# FuseCircuit.net
KiCad netlist of a schematic drawn in Altium Designer
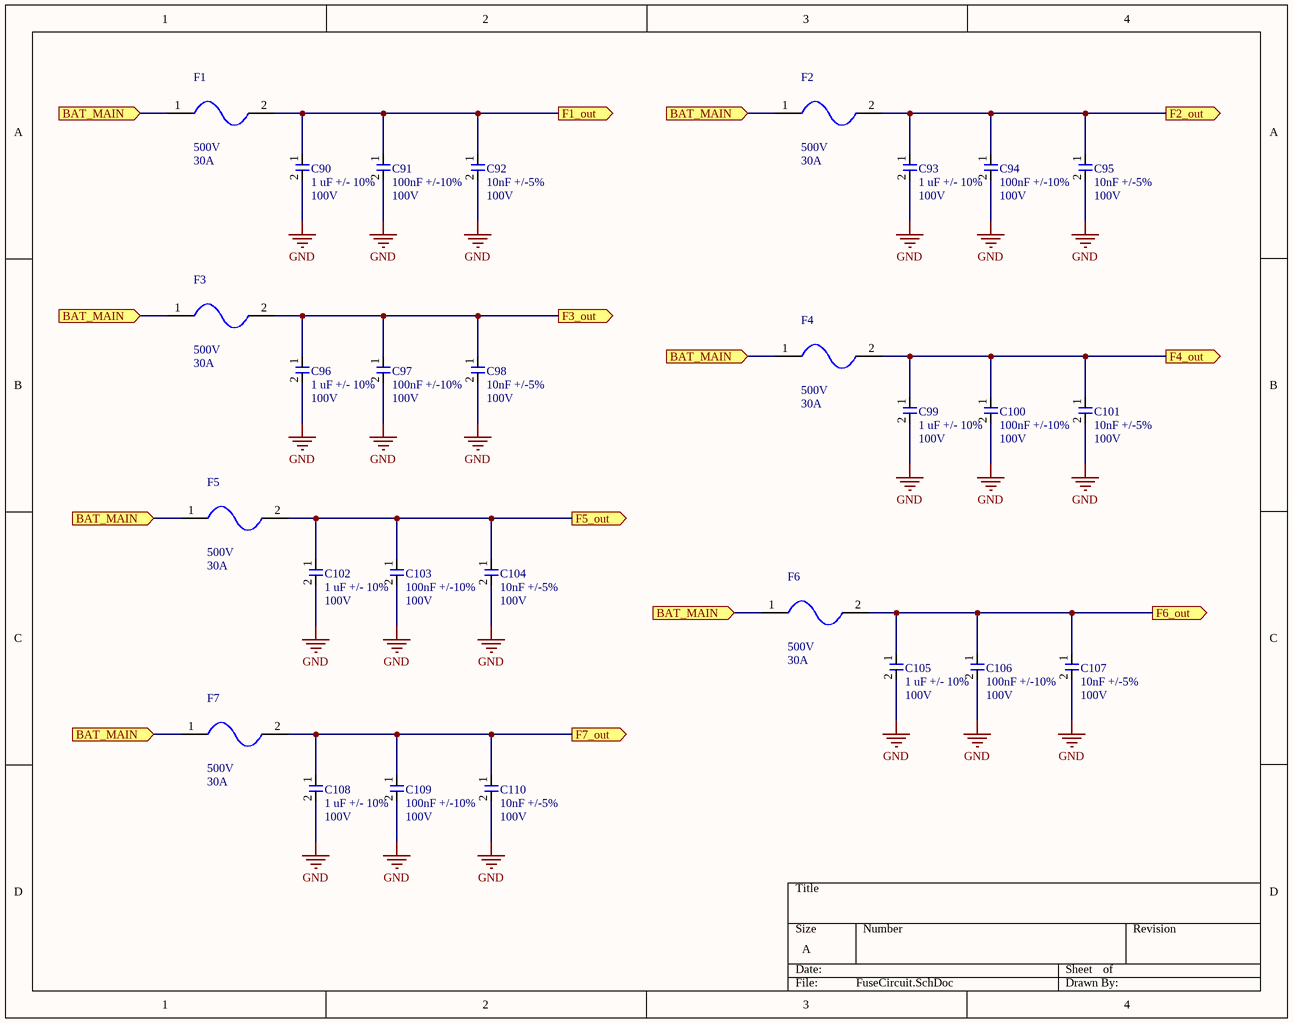
[diagram p0: FuseCircuit.SchDoc]

(export (version "E")
  (design (tool "Eeschema 10.0.6"))
  (components
    (comp (ref "C90")
      (value "CL31B105KCHNNNE")
      (footprint "CAP-1206 - duplicate")
      (description "1 µF ±10% 100V Ceramic Capacitor X7R 1206 (3216 Metric)")
      (fields (field (name "CAPACITANCE") "1 uF +/- 10%") (field (name "VOLTAGE") "100V"))
      (libsource (lib "MasterLib") (part "CAP-1U-0001"))
    )
    (comp (ref "C91")
      (value "CC0603KRX7R0BB104")
      (footprint "CAP-0603")
      (description "CAP CER 0.1UF 100V X7R 0603")
      (fields
        (field (name "MANUFACTURER") "YAGEO")
        (field (name "CAPACITANCE") "100nF +/-10%")
        (field (name "VOLTAGE RATING") "100V")
      )
      (libsource (lib "MasterLib") (part "CAP-100N-0001"))
    )
    (comp (ref "C92")
      (value "C1608C0G2A103J080AC")
      (footprint "CAP-0603")
      (description "CAP CER 10000PF 100V C0G 0603")
      (fields
        (field (name "MANUFACTURER") "TDK Corporation")
        (field (name "CAPACITANCE") "10nF +/-5%")
        (field (name "VOLTAGE RATING") "100V")
      )
      (libsource (lib "MasterLib") (part "CAP-10N-0002"))
    )
    (comp (ref "C93")
      (value "CL31B105KCHNNNE")
      (footprint "CAP-1206 - duplicate")
      (description "1 µF ±10% 100V Ceramic Capacitor X7R 1206 (3216 Metric)")
      (fields (field (name "CAPACITANCE") "1 uF +/- 10%") (field (name "VOLTAGE") "100V"))
      (libsource (lib "MasterLib") (part "CAP-1U-0001"))
    )
    (comp (ref "C94")
      (value "CC0603KRX7R0BB104")
      (footprint "CAP-0603")
      (description "CAP CER 0.1UF 100V X7R 0603")
      (fields
        (field (name "MANUFACTURER") "YAGEO")
        (field (name "CAPACITANCE") "100nF +/-10%")
        (field (name "VOLTAGE RATING") "100V")
      )
      (libsource (lib "MasterLib") (part "CAP-100N-0001"))
    )
    (comp (ref "C95")
      (value "C1608C0G2A103J080AC")
      (footprint "CAP-0603")
      (description "CAP CER 10000PF 100V C0G 0603")
      (fields
        (field (name "MANUFACTURER") "TDK Corporation")
        (field (name "CAPACITANCE") "10nF +/-5%")
        (field (name "VOLTAGE RATING") "100V")
      )
      (libsource (lib "MasterLib") (part "CAP-10N-0002"))
    )
    (comp (ref "C96")
      (value "CL31B105KCHNNNE")
      (footprint "CAP-1206 - duplicate")
      (description "1 µF ±10% 100V Ceramic Capacitor X7R 1206 (3216 Metric)")
      (fields (field (name "CAPACITANCE") "1 uF +/- 10%") (field (name "VOLTAGE") "100V"))
      (libsource (lib "MasterLib") (part "CAP-1U-0001"))
    )
    (comp (ref "C97")
      (value "CC0603KRX7R0BB104")
      (footprint "CAP-0603")
      (description "CAP CER 0.1UF 100V X7R 0603")
      (fields
        (field (name "MANUFACTURER") "YAGEO")
        (field (name "CAPACITANCE") "100nF +/-10%")
        (field (name "VOLTAGE RATING") "100V")
      )
      (libsource (lib "MasterLib") (part "CAP-100N-0001"))
    )
    (comp (ref "C98")
      (value "C1608C0G2A103J080AC")
      (footprint "CAP-0603")
      (description "CAP CER 10000PF 100V C0G 0603")
      (fields
        (field (name "MANUFACTURER") "TDK Corporation")
        (field (name "CAPACITANCE") "10nF +/-5%")
        (field (name "VOLTAGE RATING") "100V")
      )
      (libsource (lib "MasterLib") (part "CAP-10N-0002"))
    )
    (comp (ref "C99")
      (value "CL31B105KCHNNNE")
      (footprint "CAP-1206 - duplicate")
      (description "1 µF ±10% 100V Ceramic Capacitor X7R 1206 (3216 Metric)")
      (fields (field (name "CAPACITANCE") "1 uF +/- 10%") (field (name "VOLTAGE") "100V"))
      (libsource (lib "MasterLib") (part "CAP-1U-0001"))
    )
    (comp (ref "C100")
      (value "CC0603KRX7R0BB104")
      (footprint "CAP-0603")
      (description "CAP CER 0.1UF 100V X7R 0603")
      (fields
        (field (name "MANUFACTURER") "YAGEO")
        (field (name "CAPACITANCE") "100nF +/-10%")
        (field (name "VOLTAGE RATING") "100V")
      )
      (libsource (lib "MasterLib") (part "CAP-100N-0001"))
    )
    (comp (ref "C101")
      (value "C1608C0G2A103J080AC")
      (footprint "CAP-0603")
      (description "CAP CER 10000PF 100V C0G 0603")
      (fields
        (field (name "MANUFACTURER") "TDK Corporation")
        (field (name "CAPACITANCE") "10nF +/-5%")
        (field (name "VOLTAGE RATING") "100V")
      )
      (libsource (lib "MasterLib") (part "CAP-10N-0002"))
    )
    (comp (ref "C102")
      (value "CL31B105KCHNNNE")
      (footprint "CAP-1206 - duplicate")
      (description "1 µF ±10% 100V Ceramic Capacitor X7R 1206 (3216 Metric)")
      (fields (field (name "CAPACITANCE") "1 uF +/- 10%") (field (name "VOLTAGE") "100V"))
      (libsource (lib "MasterLib") (part "CAP-1U-0001"))
    )
    (comp (ref "C103")
      (value "CC0603KRX7R0BB104")
      (footprint "CAP-0603")
      (description "CAP CER 0.1UF 100V X7R 0603")
      (fields
        (field (name "MANUFACTURER") "YAGEO")
        (field (name "CAPACITANCE") "100nF +/-10%")
        (field (name "VOLTAGE RATING") "100V")
      )
      (libsource (lib "MasterLib") (part "CAP-100N-0001"))
    )
    (comp (ref "C104")
      (value "C1608C0G2A103J080AC")
      (footprint "CAP-0603")
      (description "CAP CER 10000PF 100V C0G 0603")
      (fields
        (field (name "MANUFACTURER") "TDK Corporation")
        (field (name "CAPACITANCE") "10nF +/-5%")
        (field (name "VOLTAGE RATING") "100V")
      )
      (libsource (lib "MasterLib") (part "CAP-10N-0002"))
    )
    (comp (ref "C105")
      (value "CL31B105KCHNNNE")
      (footprint "CAP-1206 - duplicate")
      (description "1 µF ±10% 100V Ceramic Capacitor X7R 1206 (3216 Metric)")
      (fields (field (name "CAPACITANCE") "1 uF +/- 10%") (field (name "VOLTAGE") "100V"))
      (libsource (lib "MasterLib") (part "CAP-1U-0001"))
    )
    (comp (ref "C106")
      (value "CC0603KRX7R0BB104")
      (footprint "CAP-0603")
      (description "CAP CER 0.1UF 100V X7R 0603")
      (fields
        (field (name "MANUFACTURER") "YAGEO")
        (field (name "CAPACITANCE") "100nF +/-10%")
        (field (name "VOLTAGE RATING") "100V")
      )
      (libsource (lib "MasterLib") (part "CAP-100N-0001"))
    )
    (comp (ref "C107")
      (value "C1608C0G2A103J080AC")
      (footprint "CAP-0603")
      (description "CAP CER 10000PF 100V C0G 0603")
      (fields
        (field (name "MANUFACTURER") "TDK Corporation")
        (field (name "CAPACITANCE") "10nF +/-5%")
        (field (name "VOLTAGE RATING") "100V")
      )
      (libsource (lib "MasterLib") (part "CAP-10N-0002"))
    )
    (comp (ref "C108")
      (value "CL31B105KCHNNNE")
      (footprint "CAP-1206 - duplicate")
      (description "1 µF ±10% 100V Ceramic Capacitor X7R 1206 (3216 Metric)")
      (fields (field (name "CAPACITANCE") "1 uF +/- 10%") (field (name "VOLTAGE") "100V"))
      (libsource (lib "MasterLib") (part "CAP-1U-0001"))
    )
    (comp (ref "C109")
      (value "CC0603KRX7R0BB104")
      (footprint "CAP-0603")
      (description "CAP CER 0.1UF 100V X7R 0603")
      (fields
        (field (name "MANUFACTURER") "YAGEO")
        (field (name "CAPACITANCE") "100nF +/-10%")
        (field (name "VOLTAGE RATING") "100V")
      )
      (libsource (lib "MasterLib") (part "CAP-100N-0001"))
    )
    (comp (ref "C110")
      (value "C1608C0G2A103J080AC")
      (footprint "CAP-0603")
      (description "CAP CER 10000PF 100V C0G 0603")
      (fields
        (field (name "MANUFACTURER") "TDK Corporation")
        (field (name "CAPACITANCE") "10nF +/-5%")
        (field (name "VOLTAGE RATING") "100V")
      )
      (libsource (lib "MasterLib") (part "CAP-10N-0002"))
    )
    (comp (ref "F1")
      (value "3568")
      (footprint "FUSE-ATM-0001")
      (description "Fuse Holder 30 A 500V 1 Circuit Blade Through Hole")
      (fields (field (name "VOLTAGE RATING") "500V") (field (name "CURRENT") "30A"))
      (libsource (lib "MasterLib") (part "FUSE-ATM-0001"))
    )
    (comp (ref "F2")
      (value "3568")
      (footprint "FUSE-ATM-0001")
      (description "Fuse Holder 30 A 500V 1 Circuit Blade Through Hole")
      (fields (field (name "VOLTAGE RATING") "500V") (field (name "CURRENT") "30A"))
      (libsource (lib "MasterLib") (part "FUSE-ATM-0001"))
    )
    (comp (ref "F3")
      (value "3568")
      (footprint "FUSE-ATM-0001")
      (description "Fuse Holder 30 A 500V 1 Circuit Blade Through Hole")
      (fields (field (name "VOLTAGE RATING") "500V") (field (name "CURRENT") "30A"))
      (libsource (lib "MasterLib") (part "FUSE-ATM-0001"))
    )
    (comp (ref "F4")
      (value "3568")
      (footprint "FUSE-ATM-0001")
      (description "Fuse Holder 30 A 500V 1 Circuit Blade Through Hole")
      (fields (field (name "VOLTAGE RATING") "500V") (field (name "CURRENT") "30A"))
      (libsource (lib "MasterLib") (part "FUSE-ATM-0001"))
    )
    (comp (ref "F5")
      (value "3568")
      (footprint "FUSE-ATM-0001")
      (description "Fuse Holder 30 A 500V 1 Circuit Blade Through Hole")
      (fields (field (name "VOLTAGE RATING") "500V") (field (name "CURRENT") "30A"))
      (libsource (lib "MasterLib") (part "FUSE-ATM-0001"))
    )
    (comp (ref "F6")
      (value "3568")
      (footprint "FUSE-ATM-0001")
      (description "Fuse Holder 30 A 500V 1 Circuit Blade Through Hole")
      (fields (field (name "VOLTAGE RATING") "500V") (field (name "CURRENT") "30A"))
      (libsource (lib "MasterLib") (part "FUSE-ATM-0001"))
    )
    (comp (ref "F7")
      (value "3568")
      (footprint "FUSE-ATM-0001")
      (description "Fuse Holder 30 A 500V 1 Circuit Blade Through Hole")
      (fields (field (name "VOLTAGE RATING") "500V") (field (name "CURRENT") "30A"))
      (libsource (lib "MasterLib") (part "FUSE-ATM-0001"))
    )
  )
  (nets
    (net (code "1") (name "/BAT_MAIN") (class "Default")
      (node (ref "F1") (pin "1") (pinfunction "0_1") (pintype "passive"))
      (node (ref "F2") (pin "1") (pinfunction "0_1") (pintype "passive"))
      (node (ref "F3") (pin "1") (pinfunction "0_1") (pintype "passive"))
      (node (ref "F4") (pin "1") (pinfunction "0_1") (pintype "passive"))
      (node (ref "F5") (pin "1") (pinfunction "0_1") (pintype "passive"))
      (node (ref "F6") (pin "1") (pinfunction "0_1") (pintype "passive"))
      (node (ref "F7") (pin "1") (pinfunction "0_1") (pintype "passive"))
    )
    (net (code "2") (name "/F1_out") (class "Default")
      (node (ref "C90") (pin "1") (pinfunction "1_1") (pintype "passive"))
      (node (ref "C91") (pin "1") (pinfunction "1_1") (pintype "passive"))
      (node (ref "C92") (pin "1") (pinfunction "1_1") (pintype "passive"))
      (node (ref "F1") (pin "2") (pinfunction "1_2") (pintype "passive"))
    )
    (net (code "3") (name "/F2_out") (class "Default")
      (node (ref "C93") (pin "1") (pinfunction "1_1") (pintype "passive"))
      (node (ref "C94") (pin "1") (pinfunction "1_1") (pintype "passive"))
      (node (ref "C95") (pin "1") (pinfunction "1_1") (pintype "passive"))
      (node (ref "F2") (pin "2") (pinfunction "1_2") (pintype "passive"))
    )
    (net (code "4") (name "/F3_out") (class "Default")
      (node (ref "C96") (pin "1") (pinfunction "1_1") (pintype "passive"))
      (node (ref "C97") (pin "1") (pinfunction "1_1") (pintype "passive"))
      (node (ref "C98") (pin "1") (pinfunction "1_1") (pintype "passive"))
      (node (ref "F3") (pin "2") (pinfunction "1_2") (pintype "passive"))
    )
    (net (code "5") (name "/F4_out") (class "Default")
      (node (ref "C100") (pin "1") (pinfunction "1_1") (pintype "passive"))
      (node (ref "C101") (pin "1") (pinfunction "1_1") (pintype "passive"))
      (node (ref "C99") (pin "1") (pinfunction "1_1") (pintype "passive"))
      (node (ref "F4") (pin "2") (pinfunction "1_2") (pintype "passive"))
    )
    (net (code "6") (name "/F5_out") (class "Default")
      (node (ref "C102") (pin "1") (pinfunction "1_1") (pintype "passive"))
      (node (ref "C103") (pin "1") (pinfunction "1_1") (pintype "passive"))
      (node (ref "C104") (pin "1") (pinfunction "1_1") (pintype "passive"))
      (node (ref "F5") (pin "2") (pinfunction "1_2") (pintype "passive"))
    )
    (net (code "7") (name "/F6_out") (class "Default")
      (node (ref "C105") (pin "1") (pinfunction "1_1") (pintype "passive"))
      (node (ref "C106") (pin "1") (pinfunction "1_1") (pintype "passive"))
      (node (ref "C107") (pin "1") (pinfunction "1_1") (pintype "passive"))
      (node (ref "F6") (pin "2") (pinfunction "1_2") (pintype "passive"))
    )
    (net (code "8") (name "/F7_out") (class "Default")
      (node (ref "C108") (pin "1") (pinfunction "1_1") (pintype "passive"))
      (node (ref "C109") (pin "1") (pinfunction "1_1") (pintype "passive"))
      (node (ref "C110") (pin "1") (pinfunction "1_1") (pintype "passive"))
      (node (ref "F7") (pin "2") (pinfunction "1_2") (pintype "passive"))
    )
    (net (code "9") (name "GND") (class "Default")
      (node (ref "C100") (pin "2") (pinfunction "2_2") (pintype "passive"))
      (node (ref "C101") (pin "2") (pinfunction "2_2") (pintype "passive"))
      (node (ref "C102") (pin "2") (pinfunction "2_2") (pintype "passive"))
      (node (ref "C103") (pin "2") (pinfunction "2_2") (pintype "passive"))
      (node (ref "C104") (pin "2") (pinfunction "2_2") (pintype "passive"))
      (node (ref "C105") (pin "2") (pinfunction "2_2") (pintype "passive"))
      (node (ref "C106") (pin "2") (pinfunction "2_2") (pintype "passive"))
      (node (ref "C107") (pin "2") (pinfunction "2_2") (pintype "passive"))
      (node (ref "C108") (pin "2") (pinfunction "2_2") (pintype "passive"))
      (node (ref "C109") (pin "2") (pinfunction "2_2") (pintype "passive"))
      (node (ref "C110") (pin "2") (pinfunction "2_2") (pintype "passive"))
      (node (ref "C90") (pin "2") (pinfunction "2_2") (pintype "passive"))
      (node (ref "C91") (pin "2") (pinfunction "2_2") (pintype "passive"))
      (node (ref "C92") (pin "2") (pinfunction "2_2") (pintype "passive"))
      (node (ref "C93") (pin "2") (pinfunction "2_2") (pintype "passive"))
      (node (ref "C94") (pin "2") (pinfunction "2_2") (pintype "passive"))
      (node (ref "C95") (pin "2") (pinfunction "2_2") (pintype "passive"))
      (node (ref "C96") (pin "2") (pinfunction "2_2") (pintype "passive"))
      (node (ref "C97") (pin "2") (pinfunction "2_2") (pintype "passive"))
      (node (ref "C98") (pin "2") (pinfunction "2_2") (pintype "passive"))
      (node (ref "C99") (pin "2") (pinfunction "2_2") (pintype "passive"))
    )
  )
)
